# LaserDiode.net
KiCad netlist of a schematic drawn in Altium Designer
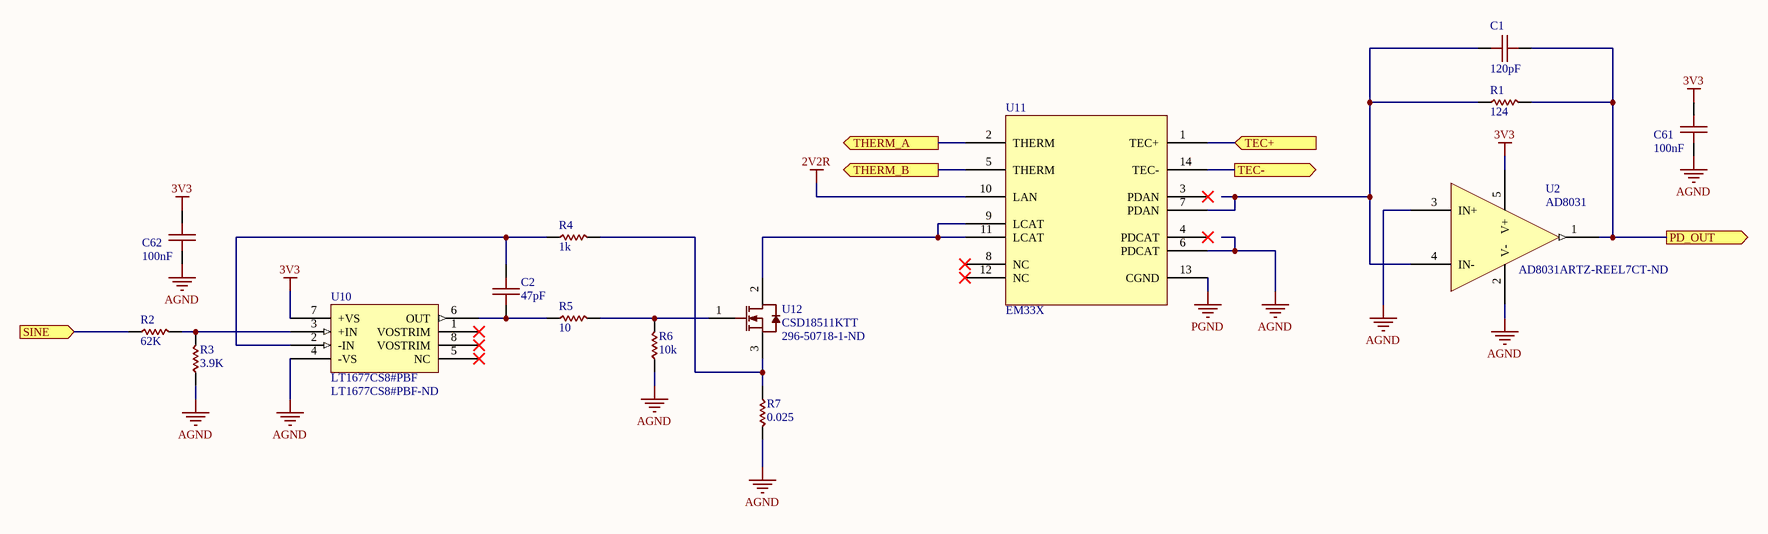
[diagram p0: LaserDiode.SchDoc]

(export (version "E")
  (design (tool "Eeschema 10.0.6"))
  (components
    (comp (ref "C1")
      (value "120pF")
      (footprint "0603 B")
      (description "603 Capacitor")
      (libsource (lib "PSSL3") (part "CAP 0603"))
    )
    (comp (ref "C2")
      (value "47pF")
      (footprint "0603 B")
      (description "603 Capacitor")
      (libsource (lib "PSSL3") (part "CAP 0603"))
    )
    (comp (ref "C61")
      (value "100nF")
      (footprint "0603 B")
      (description "603 Capacitor")
      (libsource (lib "PSSL3") (part "CAP 0603"))
    )
    (comp (ref "C62")
      (value "100nF")
      (footprint "0603 B")
      (description "603 Capacitor")
      (libsource (lib "PSSL3") (part "CAP 0603"))
    )
    (comp (ref "R1")
      (value "124")
      (footprint "0805")
      (description "805 Resistor")
      (libsource (lib "PSSL3") (part "RES 0805"))
    )
    (comp (ref "R2")
      (value "62K")
      (footprint "0805")
      (description "805 Resistor")
      (libsource (lib "PSSL3") (part "RES 0805"))
    )
    (comp (ref "R3")
      (value "3.9K")
      (footprint "0805")
      (description "805 Resistor")
      (libsource (lib "PSSL3") (part "RES 0805"))
    )
    (comp (ref "R4")
      (value "1k")
      (footprint "0805")
      (description "805 Resistor")
      (libsource (lib "PSSL3") (part "RES 0805"))
    )
    (comp (ref "R5")
      (value "10")
      (footprint "0805")
      (description "805 Resistor")
      (libsource (lib "PSSL3") (part "RES 0805"))
    )
    (comp (ref "R6")
      (value "10k")
      (footprint "0805")
      (description "805 Resistor")
      (libsource (lib "PSSL3") (part "RES 0805"))
    )
    (comp (ref "R7")
      (value "0.025")
      (footprint "1206")
      (description "1206 Resistor")
      (libsource (lib "PSSL3") (part "RES 1206"))
    )
    (comp (ref "U2")
      (value "AD8031")
      (footprint "TSOT-23-5")
      (description "2.7V, 800 uA, 80 MHz Rail-to-Rail I/O Amplifiers")
      (fields (field (name "SUPPLIER PART NUMBER 1") "AD8031ARTZ-REEL7CT-ND"))
      (libsource (lib "BeaconBoard") (part "AD8031"))
    )
    (comp (ref "U10")
      (value "LT1677CS8#PBF")
      (footprint "SO-8_S_LIT")
      (description "Low Noise, Rail-to-Rail Precision Op Amp")
      (fields
        (field (name "SUPPLIER PART NUMBER 1") "LT1677CS8#PBF-ND")
        (field (name "COPYRIGHT") "Copyright (C) 2018 Accelerated Designs. All rights reserved")
      )
      (libsource (lib "BeaconBoard") (part "LT1677CS8#PBF"))
    )
    (comp (ref "U11")
      (value "EM33X")
      (footprint "AC1409")
      (description "5W Cooled 9XX Multimode Lasers in 14-Pin Package")
      (libsource (lib "BeaconBoard") (part "EM33X"))
    )
    (comp (ref "U12")
      (value "CSD18511KTT")
      (footprint "DPAK")
      (description "40-V, N channel NexFET™ power MOSFET, single D2PAK, 2.6 mOhm")
      (fields
        (field (name "SUPPLIER PART NUMBER 1") "296-50718-1-ND")
        (field (name "COPYRIGHT") "Copyright (C) 2018 Accelerated Designs. All rights reserved")
      )
      (libsource (lib "BeaconBoard") (part "CSD18511KTT"))
    )
  )
  (nets
    (net (code "1") (name "/PD_OUT") (class "Default")
      (node (ref "C1") (pin "1") (pintype "passive"))
      (node (ref "R1") (pin "1") (pintype "passive"))
      (node (ref "U2") (pin "1") (pinfunction "OUT_1") (pintype "output"))
    )
    (net (code "2") (name "/SINE") (class "Default") (node (ref "R2") (pin "2") (pintype "passive")))
    (net (code "3") (name "/TEC+") (class "Default")
      (node (ref "U11") (pin "1") (pinfunction "TEC+_1") (pintype "passive"))
    )
    (net (code "4") (name "/TEC-") (class "Default")
      (node (ref "U11") (pin "14") (pinfunction "TEC-_14") (pintype "passive"))
    )
    (net (code "5") (name "/THERM_A") (class "Default")
      (node (ref "U11") (pin "2") (pinfunction "THERM_2") (pintype "passive"))
    )
    (net (code "6") (name "/THERM_B") (class "Default")
      (node (ref "U11") (pin "5") (pinfunction "THERM_5") (pintype "passive"))
    )
    (net (code "7") (name "2V2R") (class "Default")
      (node (ref "U11") (pin "10") (pinfunction "LAN_10") (pintype "passive"))
    )
    (net (code "8") (name "3V3") (class "Default")
      (node (ref "C61") (pin "1") (pintype "passive"))
      (node (ref "C62") (pin "1") (pintype "passive"))
      (node (ref "U10") (pin "7") (pinfunction "+VS_7") (pintype "power_in"))
      (node (ref "U2") (pin "5") (pinfunction "V+_5") (pintype "passive"))
    )
    (net (code "9") (name "AGND") (class "Default")
      (node (ref "C61") (pin "2") (pintype "passive"))
      (node (ref "C62") (pin "2") (pintype "passive"))
      (node (ref "R3") (pin "2") (pintype "passive"))
      (node (ref "R6") (pin "2") (pintype "passive"))
      (node (ref "R7") (pin "1") (pintype "passive"))
      (node (ref "U10") (pin "4") (pinfunction "-VS_4") (pintype "power_in"))
      (node (ref "U11") (pin "6") (pinfunction "PDCAT_6") (pintype "passive"))
      (node (ref "U2") (pin "2") (pinfunction "V-_2") (pintype "passive"))
      (node (ref "U2") (pin "3") (pinfunction "IN+_3") (pintype "tri_state"))
    )
    (net (code "10") (name "Net-(U2-IN-)") (class "Default")
      (node (ref "C1") (pin "2") (pintype "passive"))
      (node (ref "R1") (pin "2") (pintype "passive"))
      (node (ref "U11") (pin "7") (pinfunction "PDAN_7") (pintype "passive"))
      (node (ref "U2") (pin "4") (pinfunction "IN-_4") (pintype "tri_state"))
    )
    (net (code "11") (name "Net-(U10-+IN)") (class "Default")
      (node (ref "R2") (pin "1") (pintype "passive"))
      (node (ref "R3") (pin "1") (pintype "passive"))
      (node (ref "U10") (pin "3") (pinfunction "+IN_3") (pintype "input"))
    )
    (net (code "12") (name "Net-(U10--IN)") (class "Default")
      (node (ref "C2") (pin "1") (pintype "passive"))
      (node (ref "R4") (pin "2") (pintype "passive"))
      (node (ref "U10") (pin "2") (pinfunction "-IN_2") (pintype "input"))
    )
    (net (code "13") (name "Net-(U10-OUT)") (class "Default")
      (node (ref "C2") (pin "2") (pintype "passive"))
      (node (ref "R5") (pin "2") (pintype "passive"))
      (node (ref "U10") (pin "6") (pinfunction "OUT_6") (pintype "output"))
    )
    (net (code "14") (name "Net-(U12-D)") (class "Default")
      (node (ref "U11") (pin "11") (pinfunction "LCAT_11") (pintype "passive"))
      (node (ref "U11") (pin "9") (pinfunction "LCAT_9") (pintype "passive"))
      (node (ref "U12") (pin "2") (pinfunction "D_2") (pintype "passive"))
    )
    (net (code "15") (name "Net-(U12-G)") (class "Default")
      (node (ref "R5") (pin "1") (pintype "passive"))
      (node (ref "R6") (pin "1") (pintype "passive"))
      (node (ref "U12") (pin "1") (pinfunction "G_1") (pintype "passive"))
    )
    (net (code "16") (name "Net-(U12-S)") (class "Default")
      (node (ref "R4") (pin "1") (pintype "passive"))
      (node (ref "R7") (pin "2") (pintype "passive"))
      (node (ref "U12") (pin "3") (pinfunction "S_3") (pintype "passive"))
    )
    (net (code "17") (name "PGND") (class "Default")
      (node (ref "U11") (pin "13") (pinfunction "CGND_13") (pintype "passive"))
    )
    (net (code "18") (name "unconnected-(U10-NC-Pad5)") (class "Default")
      (node (ref "U10") (pin "5") (pinfunction "NC_5") (pintype "passive+no_connect"))
    )
    (net (code "19") (name "unconnected-(U10-VOSTRIM-Pad1)") (class "Default")
      (node (ref "U10") (pin "1") (pinfunction "VOSTRIM_1") (pintype "passive+no_connect"))
    )
    (net (code "20") (name "unconnected-(U10-VOSTRIM-Pad8)") (class "Default")
      (node (ref "U10") (pin "8") (pinfunction "VOSTRIM_8") (pintype "passive+no_connect"))
    )
    (net (code "21") (name "unconnected-(U11-NC-Pad8)") (class "Default")
      (node (ref "U11") (pin "8") (pinfunction "NC_8") (pintype "passive+no_connect"))
    )
    (net (code "22") (name "unconnected-(U11-NC-Pad12)") (class "Default")
      (node (ref "U11") (pin "12") (pinfunction "NC_12") (pintype "passive+no_connect"))
    )
    (net (code "23") (name "unconnected-(U11-PDAN-Pad3)") (class "Default")
      (node (ref "U11") (pin "3") (pinfunction "PDAN_3") (pintype "passive+no_connect"))
    )
    (net (code "24") (name "unconnected-(U11-PDCAT-Pad4)") (class "Default")
      (node (ref "U11") (pin "4") (pinfunction "PDCAT_4") (pintype "passive+no_connect"))
    )
  )
)
